# uMultimeter_BUZZER_Sch.net
KiCad netlist of a schematic drawn in Altium Designer
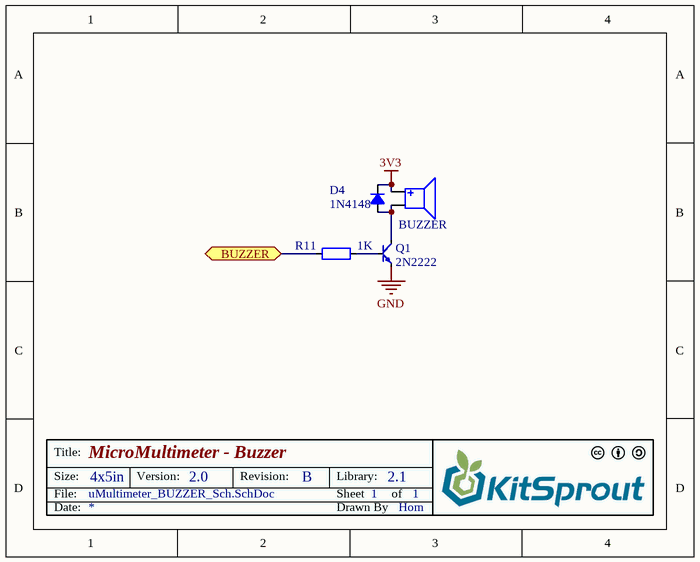
[diagram p0: uMultimeter_BUZZER_Sch.SchDoc]

(export (version "E")
  (design (tool "Eeschema 10.0.6"))
  (components
    (comp (ref "BUZZER")
      (value "Buzzer")
      (footprint "PCB_Module:Buzzer_5x5")
      (libsource (lib "SCH_Module") (part "Buzzer"))
    )
    (comp (ref "D4")
      (value "1N4148")
      (footprint "PCB_ActiveDIO:SOD-323")
      (description "Diode")
      (fields (field (name "Comment") "Diode_SOD323"))
      (libsource (lib "SCH_Active") (part "Diode_SOD323"))
    )
    (comp (ref "Q1")
      (value "2N2222")
      (footprint "PCB_IntegratedCircuit:SOT23-3")
      (description "Transistor")
      (fields (field (name "Comment") "BJT_NPN"))
      (libsource (lib "SCH_Active") (part "BJT_NPN"))
    )
    (comp (ref "R11")
      (value "1K")
      (footprint "PCB_PassiveRes:RES_0603")
      (description "Resistor")
      (fields (field (name "Comment") "Res_0603"))
      (libsource (lib "SCH_Passive") (part "Res_0603"))
    )
  )
  (nets
    (net (code "1") (name "/BUZZER") (class "Default")
      (node (ref "R11") (pin "2") (pinfunction "2_2") (pintype "passive"))
    )
    (net (code "2") (name "3V3") (class "Default")
      (node (ref "BUZZER") (pin "P") (pinfunction "Positive_P") (pintype "passive"))
      (node (ref "D4") (pin "2") (pinfunction "K_2") (pintype "passive"))
    )
    (net (code "3") (name "GND") (class "Default")
      (node (ref "Q1") (pin "2") (pinfunction "E_2") (pintype "passive"))
    )
    (net (code "4") (name "Net-(BUZZER-Negative)") (class "Default")
      (node (ref "BUZZER") (pin "N") (pinfunction "Negative_N") (pintype "passive"))
      (node (ref "D4") (pin "1") (pinfunction "A_1") (pintype "passive"))
      (node (ref "Q1") (pin "3") (pinfunction "C_3") (pintype "passive"))
    )
    (net (code "5") (name "Net-(Q1-B)") (class "Default")
      (node (ref "Q1") (pin "1") (pinfunction "B_1") (pintype "passive"))
      (node (ref "R11") (pin "1") (pinfunction "1_1") (pintype "passive"))
    )
  )
)
